# Voltage_Source.net
KiCad netlist of a schematic drawn in Altium Designer
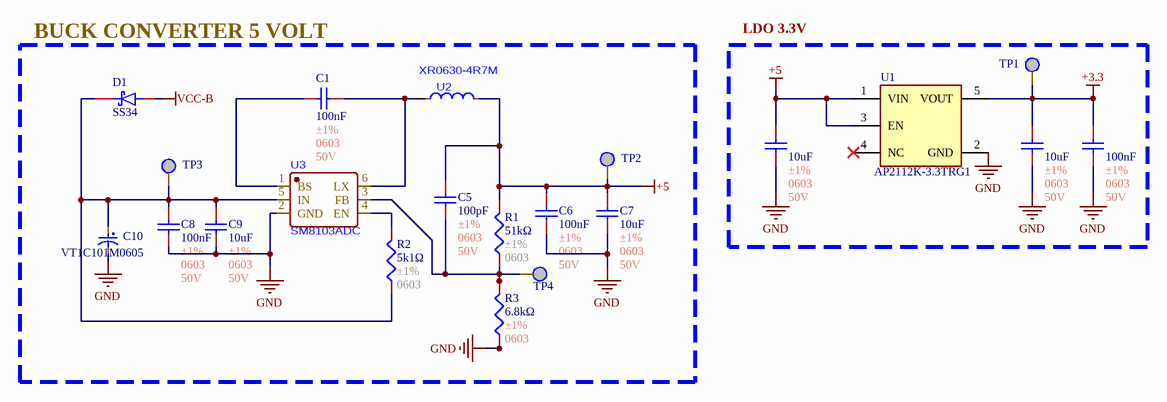
[diagram p0: Voltage Source.SchDoc]

(export (version "E")
  (design (tool "Eeschema 10.0.6"))
  (components
    (comp (ref "C1")
      (value "100nF")
      (footprint "C0603")
      (fields
        (field (name "MANUFACTURER") "YAGEO")
        (field (name "MFR. PART #") "CC0402FRNPO9BN100")
        (field (name "LCSC PART #") "C513681")
        (field (name "TOLERANCE") "±1%")
        (field (name "PACKAGE") "0603")
        (field (name "VOLTAGE RATING") "50V")
      )
      (libsource (lib "Capital") (part "C0603_100nF_±1%"))
    )
    (comp (ref "C2")
      (value "10uF")
      (footprint "C0603")
      (description "50V 10pF NP0 ±1% 0402 Multilayer Ceramic Capacitors MLCC - SMD/SMT ROHS")
      (fields
        (field (name "MANUFACTURER") "YAGEO")
        (field (name "MFR. PART #") "CC0402FRNPO9BN100")
        (field (name "TOLERANCE") "±1%")
        (field (name "PACKAGE") "0603")
        (field (name "VOLTAGE RATING") "50V")
      )
      (libsource (lib "Capital") (part "C0603_10uF_±1%"))
    )
    (comp (ref "C3")
      (value "10uF")
      (footprint "C0603")
      (description "50V 10pF NP0 ±1% 0402 Multilayer Ceramic Capacitors MLCC - SMD/SMT ROHS")
      (fields
        (field (name "MANUFACTURER") "YAGEO")
        (field (name "MFR. PART #") "CC0402FRNPO9BN100")
        (field (name "TOLERANCE") "±1%")
        (field (name "PACKAGE") "0603")
        (field (name "VOLTAGE RATING") "50V")
      )
      (libsource (lib "Capital") (part "C0603_10uF_±1%"))
    )
    (comp (ref "C4")
      (value "100nF")
      (footprint "C0603")
      (description "50V 10pF NP0 ±1% 0402 Multilayer Ceramic Capacitors MLCC - SMD/SMT ROHS")
      (fields
        (field (name "MANUFACTURER") "YAGEO")
        (field (name "MFR. PART #") "CC0402FRNPO9BN100")
        (field (name "TOLERANCE") "±1%")
        (field (name "PACKAGE") "0603")
        (field (name "VOLTAGE RATING") "50V")
      )
      (libsource (lib "Capital") (part "C0603_100nF_±1%"))
    )
    (comp (ref "C5")
      (value "100pF")
      (footprint "C0603")
      (fields
        (field (name "MANUFACTURER") "YAGEO")
        (field (name "MFR. PART #") "CC0402FRNPO9BN100")
        (field (name "LCSC PART #") "C513681")
        (field (name "TOLERANCE") "±1%")
        (field (name "PACKAGE") "0603")
        (field (name "VOLTAGE RATING") "50V")
      )
      (libsource (lib "Capital") (part "C0603_100pF_±1%"))
    )
    (comp (ref "C6")
      (value "100nF")
      (footprint "C0603")
      (fields
        (field (name "MANUFACTURER") "YAGEO")
        (field (name "MFR. PART #") "CC0402FRNPO9BN100")
        (field (name "LCSC PART #") "C513681")
        (field (name "TOLERANCE") "±1%")
        (field (name "PACKAGE") "0603")
        (field (name "VOLTAGE RATING") "50V")
      )
      (libsource (lib "Capital") (part "C0603_100nF_±1%"))
    )
    (comp (ref "C7")
      (value "10uF")
      (footprint "C0603")
      (fields
        (field (name "MANUFACTURER") "YAGEO")
        (field (name "MFR. PART #") "CC0402FRNPO9BN100")
        (field (name "LCSC PART #") "C513681")
        (field (name "TOLERANCE") "±1%")
        (field (name "PACKAGE") "0603")
        (field (name "VOLTAGE RATING") "50V")
      )
      (libsource (lib "Capital") (part "C0603_10uF_±1%"))
    )
    (comp (ref "C8")
      (value "100nF")
      (footprint "C0603")
      (fields
        (field (name "MANUFACTURER") "YAGEO")
        (field (name "MFR. PART #") "CC0402FRNPO9BN100")
        (field (name "LCSC PART #") "C513681")
        (field (name "TOLERANCE") "±1%")
        (field (name "PACKAGE") "0603")
        (field (name "VOLTAGE RATING") "50V")
      )
      (libsource (lib "Capital") (part "C0603_100nF_±1%"))
    )
    (comp (ref "C9")
      (value "10uF")
      (footprint "C0603")
      (fields
        (field (name "MANUFACTURER") "YAGEO")
        (field (name "MFR. PART #") "CC0402FRNPO9BN100")
        (field (name "LCSC PART #") "C513681")
        (field (name "TOLERANCE") "±1%")
        (field (name "PACKAGE") "0603")
        (field (name "VOLTAGE RATING") "50V")
      )
      (libsource (lib "Capital") (part "C0603_10uF_±1%"))
    )
    (comp (ref "C10")
      (value "VT1C101M0605")
      (footprint "C_100uF_16V_Aluminum")
      (description "100uF 16V ±20% 63mA@120Hz SMD,D6.3xL5.4mm Aluminum Electrolytic Capacitors RoHS")
      (fields (field (name "MANUFACTURER") "ROQANG") (field (name "LCSC PART #") "C90273"))
      (libsource (lib "Capital") (part "C_100uF_16V_aluminum"))
    )
    (comp (ref "D1")
      (value "SS34")
      (footprint "SS34")
      (description "40V Independent 3A 550mV@3A SMA(DO-214AC) Schottky Diodes ROHS")
      (fields
        (field (name "MANUFACTURER") "MDD(Microdiode Semiconductor)")
        (field (name "LCSC PART #") "C8678")
      )
      (libsource (lib "Diode") (part "SS34"))
    )
    (comp (ref "R1")
      (value "51kΩ")
      (footprint "R0603")
      (description "100mW Thick Film Resistor 75V ±100ppm/℃ ±1% 51kΩ 0603 Chip Resistor - Surface Mount ROHS")
      (fields
        (field (name "MANUFACTURER") "FOJAN")
        (field (name "MFR. PART #") "FRC0603F5101TS")
        (field (name "TOLERANCE") "±1%")
        (field (name "PACKAGE") "0603")
      )
      (libsource (lib "Resistor") (part "R0603_51kΩ_±1%"))
    )
    (comp (ref "R2")
      (value "5k1Ω")
      (footprint "R0603")
      (description "100mW Thick Film Resistor 75V ±100ppm/℃ ±1% 5.1kΩ 0603 Chip Resistor - Surface Mount ROHS")
      (fields
        (field (name "MANUFACTURER") "FOJAN")
        (field (name "MFR. PART #") "FRC0603F5101TS")
        (field (name "TOLERANCE") "±1%")
        (field (name "PACKAGE") "0603")
      )
      (libsource (lib "Resistor") (part "R0603_5k1Ω_±1%"))
    )
    (comp (ref "R3")
      (value "6.8kΩ")
      (footprint "R0603")
      (description "6.8k")
      (fields
        (field (name "MANUFACTURER") "YAGEO")
        (field (name "MFR. PART #") "RC0402FR-0710RL")
        (field (name "TOLERANCE") "±1%")
        (field (name "PACKAGE") "0603")
      )
      (libsource (lib "Resistor") (part "R0603_6.8kΩ_±1%_1"))
    )
    (comp (ref "TP1") (value "TP") (footprint "TP") (libsource (lib "Other") (part "TP")))
    (comp (ref "TP2") (value "TP") (footprint "TP") (libsource (lib "Other") (part "TP")))
    (comp (ref "TP3") (value "TP") (footprint "TP") (libsource (lib "Other") (part "TP")))
    (comp (ref "TP4") (value "TP") (footprint "TP") (libsource (lib "Other") (part "TP")))
    (comp (ref "U1")
      (value "AP2112K-3.3TRG1")
      (footprint "SOT23-5")
      (description "Linear Voltage Regulator IC Positive Fixed 1 Output 600mA SOT23-5")
      (fields (field (name "MF") "Diodes Inc."))
      (libsource (lib "My Library") (part "AP2112K-3.3TRG1"))
    )
    (comp (ref "U2")
      (value "XR0630-4R7M")
      (footprint "SMD,7x6.6mm")
      (description "FIXED IND 4.7uH 6A 33mΩ SMD,0630")
      (fields (field (name "MANUFACTURER") "XR") (field (name "LCSC PART #") "C5307631"))
      (libsource (lib "Inductor") (part "FIXED IND 4.7uH 6A 33mΩ SMD,0630"))
    )
    (comp (ref "U3")
      (value "SM8103ADC")
      (footprint "TSOT-23-6")
      (description "High Efficiency, 3.0A, 18V Input Synchronous Step Down Regulator")
      (fields (field (name "MANUFACTURER") "Silergy") (field (name "LCSC PART #") "C479070"))
      (libsource (lib "IC") (part "SM8103ADC"))
    )
  )
  (nets
    (net (code "1") (name "+3.3") (class "Default")
      (node (ref "C3") (pin "1") (pinfunction "1_1") (pintype "passive"))
      (node (ref "C4") (pin "1") (pinfunction "1_1") (pintype "passive"))
      (node (ref "TP1") (pin "1") (pinfunction "1_1") (pintype "passive"))
      (node (ref "U1") (pin "5") (pinfunction "VOUT_5") (pintype "power_in"))
    )
    (net (code "2") (name "+5") (class "Default")
      (node (ref "C2") (pin "1") (pinfunction "1_1") (pintype "passive"))
      (node (ref "C5") (pin "1") (pinfunction "1_1") (pintype "passive"))
      (node (ref "C6") (pin "1") (pinfunction "1_1") (pintype "passive"))
      (node (ref "C7") (pin "1") (pinfunction "1_1") (pintype "passive"))
      (node (ref "R1") (pin "2") (pinfunction "2_2") (pintype "passive"))
      (node (ref "TP2") (pin "1") (pinfunction "1_1") (pintype "passive"))
      (node (ref "U1") (pin "1") (pinfunction "VIN_1") (pintype "power_in"))
      (node (ref "U1") (pin "3") (pinfunction "EN_3") (pintype "passive"))
      (node (ref "U2") (pin "2") (pinfunction "F_2") (pintype "passive"))
    )
    (net (code "3") (name "GND") (class "Default")
      (node (ref "C10") (pin "2") (pinfunction "2_2") (pintype "passive"))
      (node (ref "C2") (pin "2") (pinfunction "2_2") (pintype "passive"))
      (node (ref "C3") (pin "2") (pinfunction "2_2") (pintype "passive"))
      (node (ref "C4") (pin "2") (pinfunction "2_2") (pintype "passive"))
      (node (ref "C6") (pin "2") (pinfunction "2_2") (pintype "passive"))
      (node (ref "C7") (pin "2") (pinfunction "2_2") (pintype "passive"))
      (node (ref "C8") (pin "2") (pinfunction "2_2") (pintype "passive"))
      (node (ref "C9") (pin "2") (pinfunction "2_2") (pintype "passive"))
      (node (ref "R3") (pin "1") (pinfunction "1_1") (pintype "passive"))
      (node (ref "U1") (pin "2") (pinfunction "GND_2") (pintype "power_in"))
      (node (ref "U3") (pin "2") (pinfunction "GND_2") (pintype "passive"))
    )
    (net (code "4") (name "Net-(U2-S)") (class "Default")
      (node (ref "C1") (pin "1") (pinfunction "1_1") (pintype "passive"))
      (node (ref "U2") (pin "1") (pinfunction "S_1") (pintype "passive"))
      (node (ref "U3") (pin "6") (pinfunction "LX_6") (pintype "passive"))
    )
    (net (code "5") (name "Net-(U3-BS)") (class "Default")
      (node (ref "C1") (pin "2") (pinfunction "2_2") (pintype "passive"))
      (node (ref "U3") (pin "1") (pinfunction "BS_1") (pintype "passive"))
    )
    (net (code "6") (name "Net-(U3-EN)") (class "Default")
      (node (ref "R2") (pin "2") (pinfunction "2_2") (pintype "passive"))
      (node (ref "U3") (pin "4") (pinfunction "EN_4") (pintype "passive"))
    )
    (net (code "7") (name "Net-(U3-FB)") (class "Default")
      (node (ref "C5") (pin "2") (pinfunction "2_2") (pintype "passive"))
      (node (ref "R1") (pin "1") (pinfunction "1_1") (pintype "passive"))
      (node (ref "R3") (pin "2") (pinfunction "2_2") (pintype "passive"))
      (node (ref "TP4") (pin "1") (pinfunction "1_1") (pintype "passive"))
      (node (ref "U3") (pin "3") (pinfunction "FB_3") (pintype "passive"))
    )
    (net (code "8") (name "Net-(U3-IN)") (class "Default")
      (node (ref "C10") (pin "1") (pinfunction "1_1") (pintype "passive"))
      (node (ref "C8") (pin "1") (pinfunction "1_1") (pintype "passive"))
      (node (ref "C9") (pin "1") (pinfunction "1_1") (pintype "passive"))
      (node (ref "D1") (pin "1") (pinfunction "1_1") (pintype "passive"))
      (node (ref "R2") (pin "1") (pinfunction "1_1") (pintype "passive"))
      (node (ref "TP3") (pin "1") (pinfunction "1_1") (pintype "passive"))
      (node (ref "U3") (pin "5") (pinfunction "IN_5") (pintype "passive"))
    )
    (net (code "9") (name "VCC-B") (class "Default")
      (node (ref "D1") (pin "2") (pinfunction "2_2") (pintype "passive"))
    )
    (net (code "10") (name "unconnected-(U1-NC-Pad4)") (class "Default")
      (node (ref "U1") (pin "4") (pinfunction "NC_4") (pintype "passive+no_connect"))
    )
  )
)
